# 02__RF_Power.net
KiCad netlist of a schematic drawn in Altium Designer
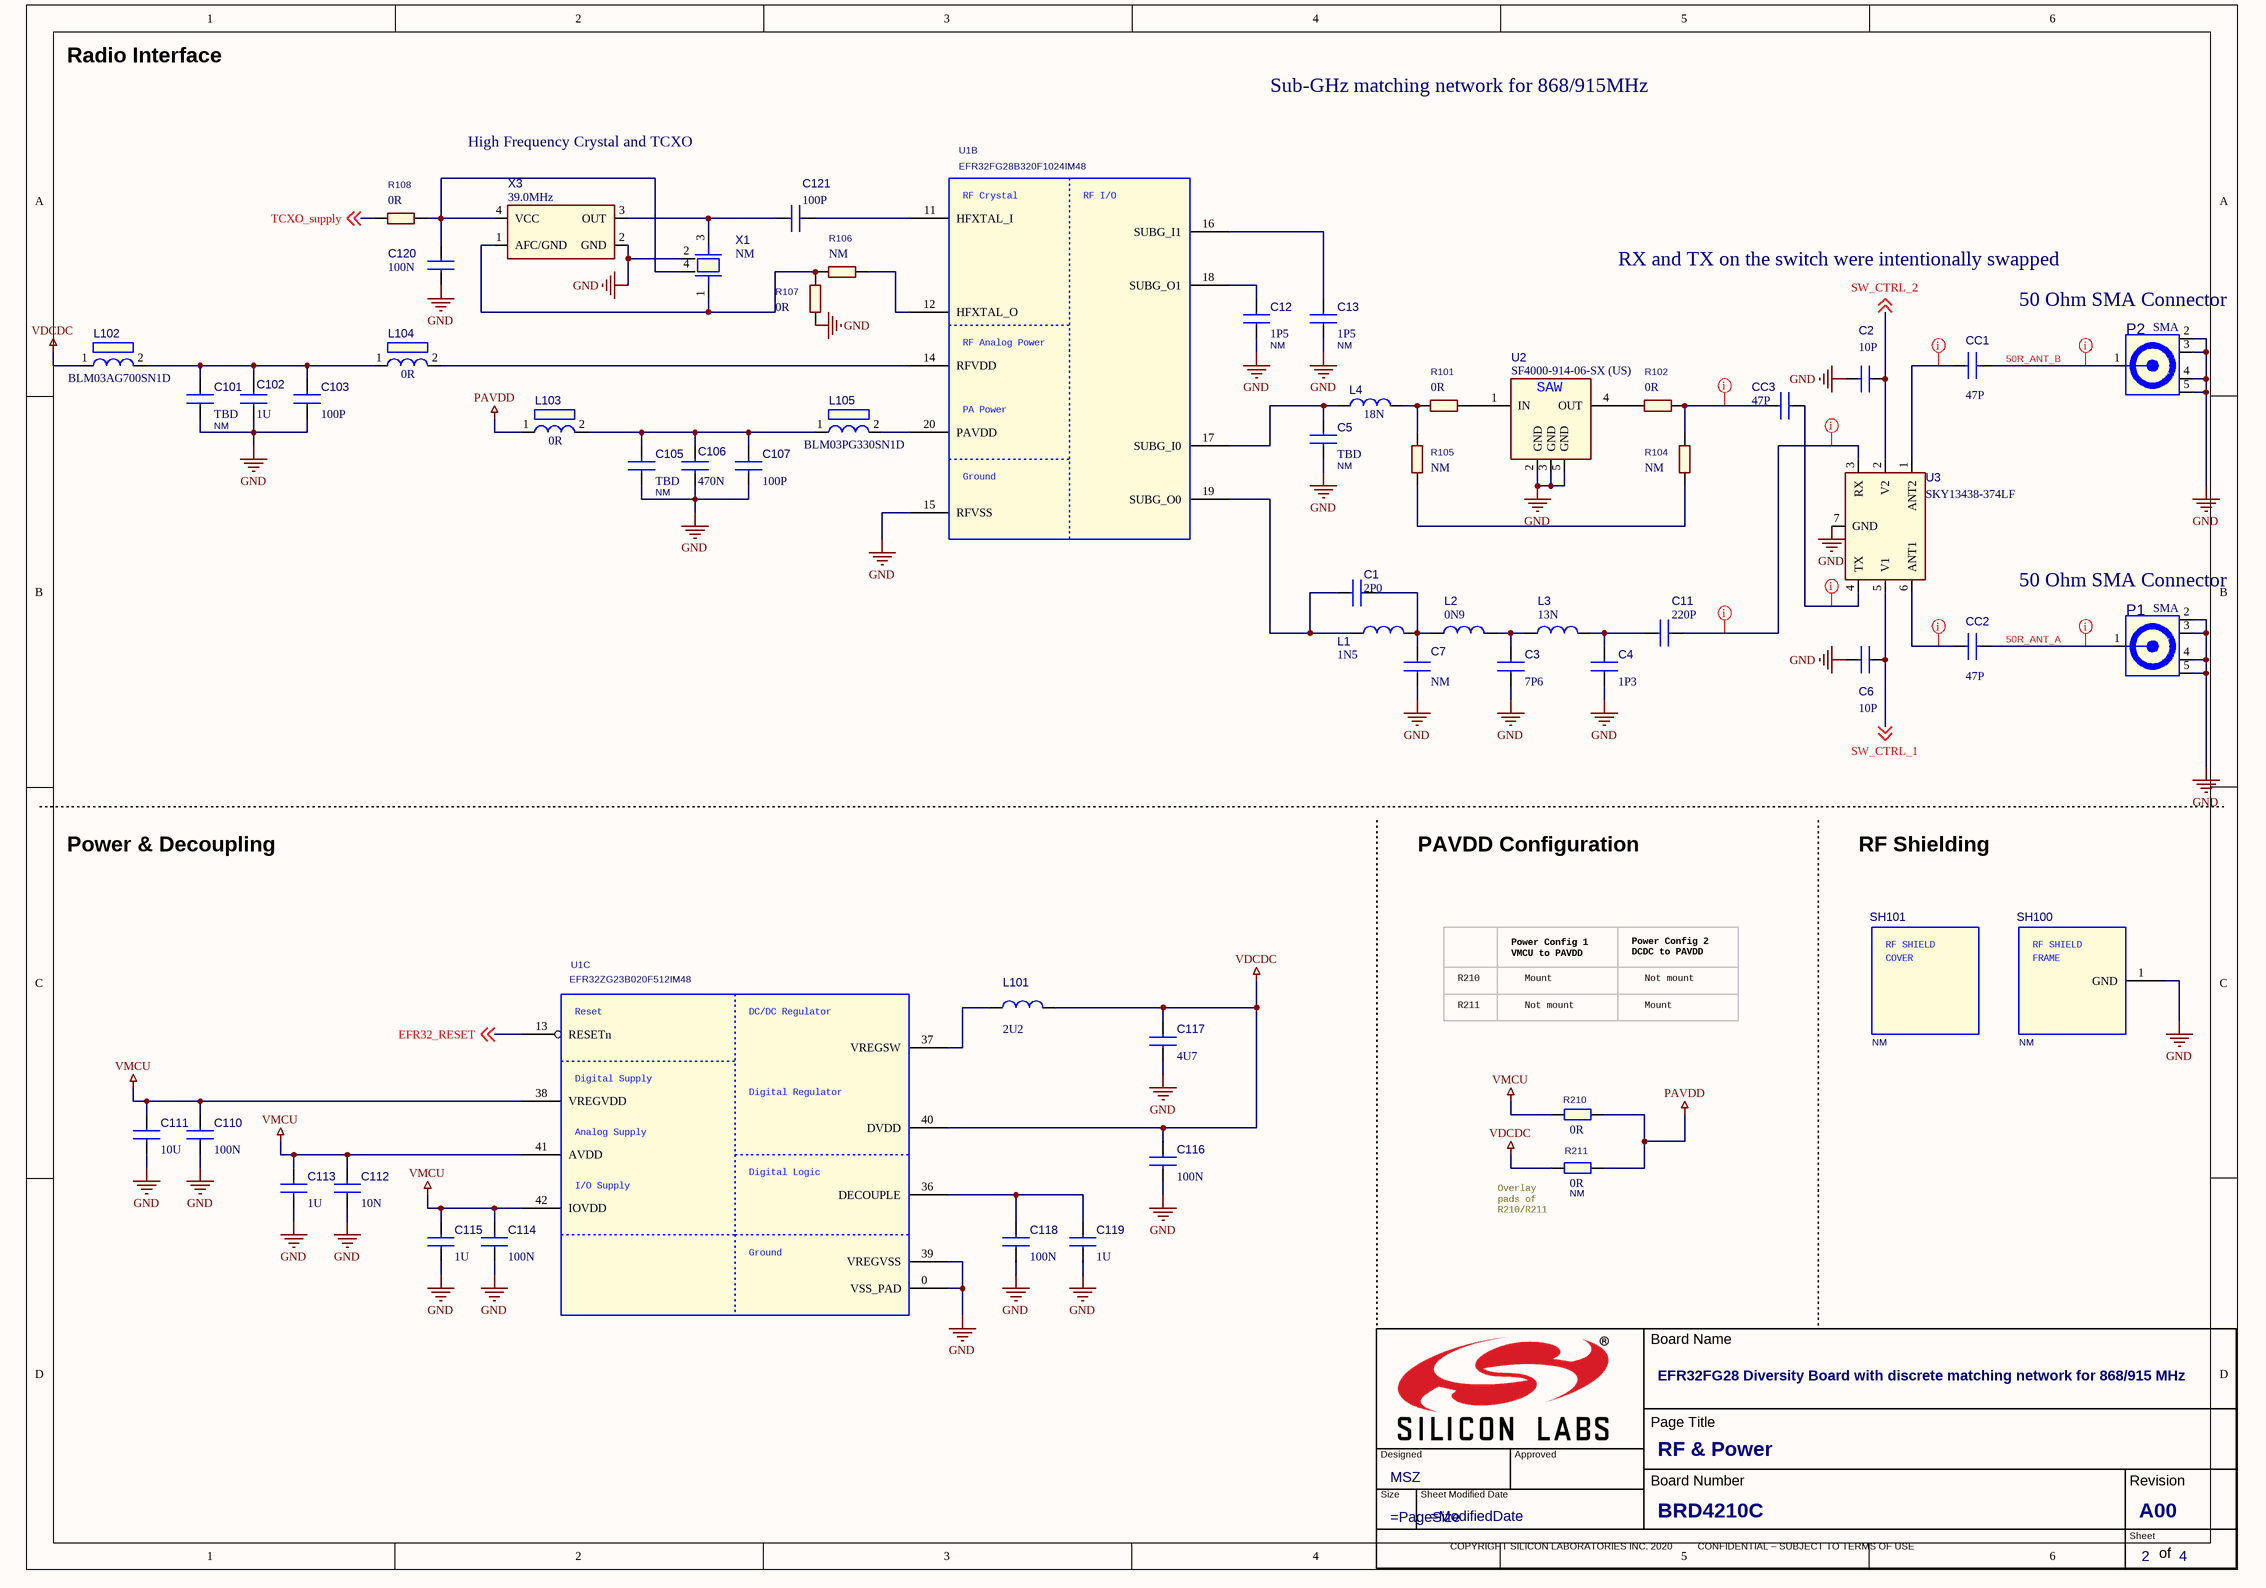
[diagram p0: 02_ RF & Power.SchDoc]

(export (version "E")
  (design (tool "Eeschema 10.0.6"))
  (components
    (comp (ref "C1")
      (value "2P0")
      (footprint "C0201_L")
      (fields (field (name "MFG") "Murata") (field (name "TOLERANCE") "±0.1pF"))
      (libsource (lib "*") (part "C0201"))
    )
    (comp (ref "C2")
      (value "10P")
      (footprint "C0201_L")
      (fields (field (name "TOLERANCE") "±2%") (field (name "MFG") "Murata"))
      (libsource (lib "*") (part "C0201"))
    )
    (comp (ref "C3")
      (value "7P6")
      (footprint "C0201_L")
      (fields (field (name "MFG") "Murata") (field (name "TOLERANCE") "±0.1pF"))
      (libsource (lib "*") (part "C0201"))
    )
    (comp (ref "C4")
      (value "1P3")
      (footprint "C0201_L")
      (fields (field (name "MFG") "Murata") (field (name "TOLERANCE") "±0.1pF"))
      (libsource (lib "*") (part "C0201"))
    )
    (comp (ref "C5")
      (value "TBD")
      (footprint "C0201_L")
      (fields (field (name "NOT MOUNTED") "NM"))
      (libsource (lib "*") (part "C0201"))
    )
    (comp (ref "C6")
      (value "10P")
      (footprint "C0201_L")
      (fields (field (name "TOLERANCE") "±2%") (field (name "MFG") "Murata"))
      (libsource (lib "*") (part "C0201"))
    )
    (comp (ref "C7")
      (value "NM")
      (footprint "C0201_L")
      (fields (field (name "MFG") "Murata") (field (name "TOLERANCE") "±0.1pF"))
      (libsource (lib "*") (part "C0201"))
    )
    (comp (ref "C11")
      (value "220P")
      (footprint "C0201_L")
      (fields (field (name "MFG") "Murata") (field (name "TOLERANCE") "±2%"))
      (libsource (lib "*") (part "C0201"))
    )
    (comp (ref "C12")
      (value "1P5")
      (footprint "C0201_L")
      (fields
        (field (name "MFG") "Murata")
        (field (name "NOT MOUNTED") "NM")
        (field (name "TOLERANCE") "±0.05pF")
      )
      (libsource (lib "*") (part "C0201"))
    )
    (comp (ref "C13")
      (value "1P5")
      (footprint "C0201_L")
      (fields
        (field (name "MFG") "Murata")
        (field (name "NOT MOUNTED") "NM")
        (field (name "TOLERANCE") "±0.05pF")
      )
      (libsource (lib "*") (part "C0201"))
    )
    (comp (ref "C101")
      (value "TBD")
      (footprint "C0201_L")
      (fields (field (name "NOT MOUNTED") "NM") (field (name "TOLERANCE") "+/-0.05P"))
      (libsource (lib "*") (part "C0201"))
    )
    (comp (ref "C102")
      (value "1U")
      (footprint "C0402_L")
      (fields (field (name "TOLERANCE") "10%"))
      (libsource (lib "*") (part "C0402"))
    )
    (comp (ref "C103")
      (value "100P")
      (footprint "C0201_L")
      (fields (field (name "TOLERANCE") "5%"))
      (libsource (lib "*") (part "C0201"))
    )
    (comp (ref "C105")
      (value "TBD")
      (footprint "C0201_L")
      (fields (field (name "NOT MOUNTED") "NM") (field (name "TOLERANCE") "+/-0.05P"))
      (libsource (lib "*") (part "C0201"))
    )
    (comp (ref "C106")
      (value "470N")
      (footprint "C0402_L")
      (fields (field (name "TOLERANCE") "10%"))
      (libsource (lib "*") (part "C0402"))
    )
    (comp (ref "C107")
      (value "100P")
      (footprint "C0201_L")
      (fields (field (name "TOLERANCE") "5%"))
      (libsource (lib "*") (part "C0201"))
    )
    (comp (ref "C110")
      (value "100N")
      (footprint "C0201_L")
      (fields (field (name "TOLERANCE") "20%"))
      (libsource (lib "*") (part "C0201"))
    )
    (comp (ref "C111")
      (value "10U")
      (footprint "C0603_L")
      (fields (field (name "TOLERANCE") "10%"))
      (libsource (lib "*") (part "C0603"))
    )
    (comp (ref "C112")
      (value "10N")
      (footprint "C0201_L")
      (fields (field (name "TOLERANCE") "10%"))
      (libsource (lib "*") (part "C0201"))
    )
    (comp (ref "C113")
      (value "1U")
      (footprint "C0402_L")
      (fields (field (name "TOLERANCE") "10%"))
      (libsource (lib "*") (part "C0402"))
    )
    (comp (ref "C114")
      (value "100N")
      (footprint "C0201_L")
      (fields (field (name "TOLERANCE") "20%"))
      (libsource (lib "*") (part "C0201"))
    )
    (comp (ref "C115")
      (value "1U")
      (footprint "C0402_L")
      (fields (field (name "TOLERANCE") "10%"))
      (libsource (lib "*") (part "C0402"))
    )
    (comp (ref "C116")
      (value "100N")
      (footprint "C0201_L")
      (fields (field (name "TOLERANCE") "20%"))
      (libsource (lib "*") (part "C0201"))
    )
    (comp (ref "C117")
      (value "4U7")
      (footprint "C0603_L")
      (fields (field (name "TOLERANCE") "10%"))
      (libsource (lib "*") (part "C0603"))
    )
    (comp (ref "C118")
      (value "100N")
      (footprint "C0201_L")
      (fields (field (name "TOLERANCE") "20%"))
      (libsource (lib "*") (part "C0201"))
    )
    (comp (ref "C119")
      (value "1U")
      (footprint "C0402_L")
      (fields (field (name "TOLERANCE") "10%"))
      (libsource (lib "*") (part "C0402"))
    )
    (comp (ref "C120")
      (value "100N")
      (footprint "C0201_L")
      (fields (field (name "MFG") "Murata") (field (name "TOLERANCE") "±0.05pF"))
      (libsource (lib "*") (part "C0201"))
    )
    (comp (ref "C121")
      (value "100P")
      (footprint "C0201_L")
      (fields (field (name "MFG") "Murata") (field (name "TOLERANCE") "±0.05pF"))
      (libsource (lib "*") (part "C0201"))
    )
    (comp (ref "CC1")
      (value "47P")
      (footprint "C0201_L")
      (fields (field (name "TOLERANCE") "±2%") (field (name "MFG") "Murata"))
      (libsource (lib "*") (part "C0201"))
    )
    (comp (ref "CC2")
      (value "47P")
      (footprint "C0201_L")
      (fields (field (name "TOLERANCE") "±2%") (field (name "MFG") "Murata"))
      (libsource (lib "*") (part "C0201"))
    )
    (comp (ref "CC3")
      (value "47P")
      (footprint "C0201_L")
      (fields (field (name "TOLERANCE") "±2%") (field (name "MFG") "Murata"))
      (libsource (lib "*") (part "C0201"))
    )
    (comp (ref "L1")
      (value "1N5")
      (footprint "COIL_0201_L")
      (fields (field (name "MFG") "Murata") (field (name "TOLERANCE") "±0.05nH"))
      (libsource (lib "*") (part "L0201"))
    )
    (comp (ref "L2")
      (value "0N9")
      (footprint "COIL_0201_L")
      (fields (field (name "MFG") "Murata") (field (name "TOLERANCE") "±0.05nH"))
      (libsource (lib "*") (part "L0201"))
    )
    (comp (ref "L3")
      (value "13N")
      (footprint "COIL_0201_L")
      (fields (field (name "MFG") "Murata") (field (name "TOLERANCE") "±3%"))
      (libsource (lib "*") (part "L0201"))
    )
    (comp (ref "L4")
      (value "18N")
      (footprint "COIL_0201_L")
      (fields (field (name "MFG") "Murata") (field (name "TOLERANCE") "±3%"))
      (libsource (lib "*") (part "L0201"))
    )
    (comp (ref "L101")
      (value "2U2")
      (footprint "COIL_1008_L")
      (fields (field (name "TOLERANCE") "+/-20%") (field (name "MFG") "Murata"))
      (libsource (lib "*") (part "L1008"))
    )
    (comp (ref "L102")
      (value "BLM03AG700SN1D")
      (footprint "COIL_MUR_BLM03_0201")
      (fields (field (name "MFG") "Murata"))
      (libsource (lib "*") (part "BLM03AX"))
    )
    (comp (ref "L103") (value "0R") (footprint "COIL_MUR_BLM03_0201") (libsource (lib "*") (part "BLM03AX")))
    (comp (ref "L104") (value "0R") (footprint "COIL_MUR_BLM03_0201") (libsource (lib "*") (part "BLM03AX")))
    (comp (ref "L105")
      (value "BLM03PG330SN1D")
      (footprint "COIL_MUR_BLM03_0201")
      (fields (field (name "MFG") "Murata"))
      (libsource (lib "*") (part "BLM03AX"))
    )
    (comp (ref "P1")
      (value "SMA")
      (footprint "TE_SMA_1814832_TH_VER")
      (fields (field (name "MFG") "Wellshow"))
      (libsource (lib "*") (part "SMA_TH_WELLSHOW"))
    )
    (comp (ref "P2")
      (value "SMA")
      (footprint "TE_SMA_1814832_TH_VER")
      (fields (field (name "MFG") "Wellshow"))
      (libsource (lib "*") (part "SMA_TH_WELLSHOW"))
    )
    (comp (ref "R101") (value "0R") (footprint "R0201_L") (libsource (lib "BRD4210A_Library") (part "R0201")))
    (comp (ref "R102") (value "0R") (footprint "R0201_L") (libsource (lib "BRD4210A_Library") (part "R0201")))
    (comp (ref "R104") (value "NM") (footprint "R0201_L") (libsource (lib "") (part "R0201_1")))
    (comp (ref "R105") (value "NM") (footprint "R0201_L") (libsource (lib "") (part "R0201_1")))
    (comp (ref "R106") (value "NM") (footprint "R0201_L") (libsource (lib "BRD4210A_Library") (part "R0201")))
    (comp (ref "R107") (value "0R") (footprint "R0201_L") (libsource (lib "") (part "R0201_1")))
    (comp (ref "R108") (value "0R") (footprint "R0201_L") (libsource (lib "BRD4210A_Library") (part "R0201")))
    (comp (ref "R210") (value "0R") (footprint "R0402_L") (libsource (lib "") (part "R0402_1")))
    (comp (ref "R211")
      (value "0R")
      (footprint "R0402_L")
      (fields (field (name "NOT MOUNTED") "NM"))
      (libsource (lib "*") (part "R0402"))
    )
    (comp (ref "SH100")
      (value "RF_SHIELD_FRAME_36103205S")
      (footprint "Shield_21x21mm")
      (fields (field (name "NOT MOUNTED") "NM") (field (name "MFG") "Würth Elektronik"))
      (libsource (lib "*") (part "RF_SHIELD_FRAME_36103205S"))
    )
    (comp (ref "SH101")
      (value "RF_SHIELD_COVER_36003200S")
      (fields (field (name "NOT MOUNTED") "NM") (field (name "MFG") "Würth Elektronik"))
      (libsource (lib "*") (part "RF_SHIELD_COVER_36003200S"))
    )
    (comp (ref "U1")
      (value "EFR32ZG23B020F512IM48")
      (footprint "QFN48_M040_6.0X6.0_EP_SL")
      (fields (field (name "MFG") "Silicon Labs"))
      (libsource (lib "*") (part "EFR32xG23_QFN48"))
    )
    (comp (ref "U2")
      (value "SF4000-914-06-SX (US)")
      (footprint "SF1256")
      (description "B2645 from Qualcomm also fits")
      (fields (field (name "MFG") "ACTE"))
      (libsource (lib "BRD4210A_Library") (part "SF4000-914-06-SX"))
    )
    (comp (ref "U3")
      (value "SKY13438-374LF")
      (footprint "SKY13438-374LF")
      (fields (field (name "MFG") "Infineon"))
      (libsource (lib "BRD4210A_Library") (part "SKY13438-374LF"))
    )
    (comp (ref "X1")
      (value "NM")
      (footprint "X_SSS_DSX211SH_2.05X1.65-4")
      (fields (field (name "MFG") "Tai-Saw"))
      (libsource (lib "*") (part "DSX211SH"))
    )
    (comp (ref "X3")
      (value "39.0MHz")
      (footprint "TCXO_7Z-38.400MBG-T_SMD2016_TXC")
      (fields (field (name "MFG") "TXC"))
      (libsource (lib "BRD4210A_Library") (part "7Z-38.400MBG-T"))
    )
  )
  (nets
    (net (code "1") (name "/50R_ANT_A") (class "Default")
      (node (ref "CC2") (pin "2") (pinfunction "2_2") (pintype "passive"))
      (node (ref "P1") (pin "1") (pinfunction "SIGNAL_1") (pintype "passive"))
    )
    (net (code "2") (name "/50R_ANT_B") (class "Default")
      (node (ref "CC1") (pin "2") (pinfunction "2_2") (pintype "passive"))
      (node (ref "P2") (pin "1") (pinfunction "SIGNAL_1") (pintype "passive"))
    )
    (net (code "3") (name "EFR32_RESET") (class "Default")
      (node (ref "U1") (pin "13") (pinfunction "RESETn_13") (pintype "passive"))
    )
    (net (code "4") (name "GND") (class "Default")
      (node (ref "C101") (pin "2") (pinfunction "2_2") (pintype "passive"))
      (node (ref "C102") (pin "2") (pinfunction "2_2") (pintype "passive"))
      (node (ref "C103") (pin "2") (pinfunction "2_2") (pintype "passive"))
      (node (ref "C105") (pin "2") (pinfunction "2_2") (pintype "passive"))
      (node (ref "C106") (pin "2") (pinfunction "2_2") (pintype "passive"))
      (node (ref "C107") (pin "2") (pinfunction "2_2") (pintype "passive"))
      (node (ref "C110") (pin "2") (pinfunction "2_2") (pintype "passive"))
      (node (ref "C111") (pin "2") (pinfunction "2_2") (pintype "passive"))
      (node (ref "C112") (pin "2") (pinfunction "2_2") (pintype "passive"))
      (node (ref "C113") (pin "2") (pinfunction "2_2") (pintype "passive"))
      (node (ref "C114") (pin "2") (pinfunction "2_2") (pintype "passive"))
      (node (ref "C115") (pin "2") (pinfunction "2_2") (pintype "passive"))
      (node (ref "C116") (pin "2") (pinfunction "2_2") (pintype "passive"))
      (node (ref "C117") (pin "2") (pinfunction "2_2") (pintype "passive"))
      (node (ref "C118") (pin "2") (pinfunction "2_2") (pintype "passive"))
      (node (ref "C119") (pin "2") (pinfunction "2_2") (pintype "passive"))
      (node (ref "C12") (pin "2") (pinfunction "2_2") (pintype "passive"))
      (node (ref "C120") (pin "2") (pinfunction "2_2") (pintype "passive"))
      (node (ref "C13") (pin "2") (pinfunction "2_2") (pintype "passive"))
      (node (ref "C2") (pin "1") (pinfunction "1_1") (pintype "passive"))
      (node (ref "C3") (pin "2") (pinfunction "2_2") (pintype "passive"))
      (node (ref "C4") (pin "2") (pinfunction "2_2") (pintype "passive"))
      (node (ref "C5") (pin "2") (pinfunction "2_2") (pintype "passive"))
      (node (ref "C6") (pin "1") (pinfunction "1_1") (pintype "passive"))
      (node (ref "C7") (pin "2") (pinfunction "2_2") (pintype "passive"))
      (node (ref "P1") (pin "2") (pinfunction "GND1_2") (pintype "passive"))
      (node (ref "P1") (pin "3") (pinfunction "GND2_3") (pintype "passive"))
      (node (ref "P1") (pin "4") (pinfunction "GND3_4") (pintype "passive"))
      (node (ref "P1") (pin "5") (pinfunction "GND4_5") (pintype "passive"))
      (node (ref "P2") (pin "2") (pinfunction "GND1_2") (pintype "passive"))
      (node (ref "P2") (pin "3") (pinfunction "GND2_3") (pintype "passive"))
      (node (ref "P2") (pin "4") (pinfunction "GND3_4") (pintype "passive"))
      (node (ref "P2") (pin "5") (pinfunction "GND4_5") (pintype "passive"))
      (node (ref "R107") (pin "2") (pinfunction "2_2") (pintype "passive"))
      (node (ref "SH100") (pin "1") (pinfunction "GND_1") (pintype "passive"))
      (node (ref "U1") (pin "0") (pinfunction "VSS_PAD_0") (pintype "power_in"))
      (node (ref "U1") (pin "15") (pinfunction "RFVSS_15") (pintype "passive"))
      (node (ref "U1") (pin "39") (pinfunction "VREGVSS_39") (pintype "passive"))
      (node (ref "U2") (pin "2") (pinfunction "GND_2") (pintype "passive"))
      (node (ref "U2") (pin "3") (pinfunction "GND_3") (pintype "passive"))
      (node (ref "U2") (pin "5") (pinfunction "GND_5") (pintype "passive"))
      (node (ref "U3") (pin "7") (pinfunction "GND_7") (pintype "passive"))
      (node (ref "X1") (pin "2") (pinfunction "2_2") (pintype "passive"))
      (node (ref "X3") (pin "2") (pinfunction "GND_2") (pintype "passive"))
    )
    (net (code "5") (name "Net-(C1-Pad2)") (class "Default")
      (node (ref "C1") (pin "2") (pinfunction "2_2") (pintype "passive"))
      (node (ref "C7") (pin "1") (pinfunction "1_1") (pintype "passive"))
      (node (ref "L1") (pin "2") (pinfunction "2_2") (pintype "passive"))
      (node (ref "L2") (pin "1") (pinfunction "1_1") (pintype "passive"))
    )
    (net (code "6") (name "Net-(C3-Pad1)") (class "Default")
      (node (ref "C3") (pin "1") (pinfunction "1_1") (pintype "passive"))
      (node (ref "L2") (pin "2") (pinfunction "2_2") (pintype "passive"))
      (node (ref "L3") (pin "1") (pinfunction "1_1") (pintype "passive"))
    )
    (net (code "7") (name "Net-(C11-Pad1)") (class "Default")
      (node (ref "C11") (pin "1") (pinfunction "1_1") (pintype "passive"))
      (node (ref "C4") (pin "1") (pinfunction "1_1") (pintype "passive"))
      (node (ref "L3") (pin "2") (pinfunction "2_2") (pintype "passive"))
    )
    (net (code "8") (name "Net-(C101-Pad1)") (class "Default")
      (node (ref "C101") (pin "1") (pinfunction "1_1") (pintype "passive"))
      (node (ref "C102") (pin "1") (pinfunction "1_1") (pintype "passive"))
      (node (ref "C103") (pin "1") (pinfunction "1_1") (pintype "passive"))
      (node (ref "L102") (pin "2") (pinfunction "2_2") (pintype "passive"))
      (node (ref "L104") (pin "1") (pinfunction "1_1") (pintype "passive"))
    )
    (net (code "9") (name "Net-(C105-Pad1)") (class "Default")
      (node (ref "C105") (pin "1") (pinfunction "1_1") (pintype "passive"))
      (node (ref "C106") (pin "1") (pinfunction "1_1") (pintype "passive"))
      (node (ref "C107") (pin "1") (pinfunction "1_1") (pintype "passive"))
      (node (ref "L103") (pin "2") (pinfunction "2_2") (pintype "passive"))
      (node (ref "L105") (pin "1") (pinfunction "1_1") (pintype "passive"))
    )
    (net (code "10") (name "Net-(CC3-Pad1)") (class "Default")
      (node (ref "CC3") (pin "1") (pinfunction "1_1") (pintype "passive"))
      (node (ref "R102") (pin "2") (pinfunction "2_2") (pintype "passive"))
      (node (ref "R104") (pin "1") (pinfunction "1_1") (pintype "passive"))
    )
    (net (code "11") (name "Net-(L4-Pad2)") (class "Default")
      (node (ref "L4") (pin "2") (pinfunction "2_2") (pintype "passive"))
      (node (ref "R101") (pin "1") (pinfunction "1_1") (pintype "passive"))
      (node (ref "R105") (pin "1") (pinfunction "1_1") (pintype "passive"))
    )
    (net (code "12") (name "Net-(R104-Pad2)") (class "Default")
      (node (ref "R104") (pin "2") (pinfunction "2_2") (pintype "passive"))
      (node (ref "R105") (pin "2") (pinfunction "2_2") (pintype "passive"))
    )
    (net (code "13") (name "Net-(U1B-HFXTAL_I)") (class "Default")
      (node (ref "C121") (pin "2") (pinfunction "2_2") (pintype "passive"))
      (node (ref "U1") (pin "11") (pinfunction "HFXTAL_I_11") (pintype "passive"))
    )
    (net (code "14") (name "Net-(U1B-HFXTAL_O)") (class "Default")
      (node (ref "R106") (pin "2") (pinfunction "2_2") (pintype "passive"))
      (node (ref "U1") (pin "12") (pinfunction "HFXTAL_O_12") (pintype "passive"))
    )
    (net (code "15") (name "Net-(U1B-PAVDD)") (class "Default")
      (node (ref "L105") (pin "2") (pinfunction "2_2") (pintype "passive"))
      (node (ref "U1") (pin "20") (pinfunction "PAVDD_20") (pintype "passive"))
    )
    (net (code "16") (name "Net-(U1B-RFVDD)") (class "Default")
      (node (ref "L104") (pin "2") (pinfunction "2_2") (pintype "passive"))
      (node (ref "U1") (pin "14") (pinfunction "RFVDD_14") (pintype "power_in"))
    )
    (net (code "17") (name "Net-(U1B-SUBG_I0)") (class "Default")
      (node (ref "C5") (pin "1") (pinfunction "1_1") (pintype "passive"))
      (node (ref "L4") (pin "1") (pinfunction "1_1") (pintype "passive"))
      (node (ref "U1") (pin "17") (pinfunction "SUBG_I0_17") (pintype "passive"))
    )
    (net (code "18") (name "Net-(U1B-SUBG_I1)") (class "Default")
      (node (ref "C13") (pin "1") (pinfunction "1_1") (pintype "passive"))
      (node (ref "U1") (pin "16") (pinfunction "SUBG_I1_16") (pintype "passive"))
    )
    (net (code "19") (name "Net-(U1B-SUBG_O0)") (class "Default")
      (node (ref "C1") (pin "1") (pinfunction "1_1") (pintype "passive"))
      (node (ref "L1") (pin "1") (pinfunction "1_1") (pintype "passive"))
      (node (ref "U1") (pin "19") (pinfunction "SUBG_O0_19") (pintype "passive"))
    )
    (net (code "20") (name "Net-(U1B-SUBG_O1)") (class "Default")
      (node (ref "C12") (pin "1") (pinfunction "1_1") (pintype "passive"))
      (node (ref "U1") (pin "18") (pinfunction "SUBG_O1_18") (pintype "passive"))
    )
    (net (code "21") (name "Net-(U1C-DECOUPLE)") (class "Default")
      (node (ref "C118") (pin "1") (pinfunction "1_1") (pintype "passive"))
      (node (ref "C119") (pin "1") (pinfunction "1_1") (pintype "passive"))
      (node (ref "U1") (pin "36") (pinfunction "DECOUPLE_36") (pintype "power_in"))
    )
    (net (code "22") (name "Net-(U1C-VREGSW)") (class "Default")
      (node (ref "L101") (pin "1") (pinfunction "1_1") (pintype "passive"))
      (node (ref "U1") (pin "37") (pinfunction "VREGSW_37") (pintype "passive"))
    )
    (net (code "23") (name "Net-(U2-IN)") (class "Default")
      (node (ref "R101") (pin "2") (pinfunction "2_2") (pintype "passive"))
      (node (ref "U2") (pin "1") (pinfunction "IN_1") (pintype "passive"))
    )
    (net (code "24") (name "Net-(U2-OUT)") (class "Default")
      (node (ref "R102") (pin "1") (pinfunction "1_1") (pintype "passive"))
      (node (ref "U2") (pin "4") (pinfunction "OUT_4") (pintype "passive"))
    )
    (net (code "25") (name "Net-(U3-ANT1)") (class "Default")
      (node (ref "CC2") (pin "1") (pinfunction "1_1") (pintype "passive"))
      (node (ref "U3") (pin "6") (pinfunction "ANT1_6") (pintype "passive"))
    )
    (net (code "26") (name "Net-(U3-ANT2)") (class "Default")
      (node (ref "CC1") (pin "1") (pinfunction "1_1") (pintype "passive"))
      (node (ref "U3") (pin "1") (pinfunction "ANT2_1") (pintype "passive"))
    )
    (net (code "27") (name "Net-(U3-RX)") (class "Default")
      (node (ref "C11") (pin "2") (pinfunction "2_2") (pintype "passive"))
      (node (ref "U3") (pin "3") (pinfunction "RX_3") (pintype "passive"))
    )
    (net (code "28") (name "Net-(U3-TX)") (class "Default")
      (node (ref "CC3") (pin "2") (pinfunction "2_2") (pintype "passive"))
      (node (ref "U3") (pin "4") (pinfunction "TX_4") (pintype "passive"))
    )
    (net (code "29") (name "Net-(X3-AFC{slash}GND)") (class "Default")
      (node (ref "R106") (pin "1") (pinfunction "1_1") (pintype "passive"))
      (node (ref "R107") (pin "1") (pinfunction "1_1") (pintype "passive"))
      (node (ref "X1") (pin "1") (pinfunction "1_1") (pintype "passive"))
      (node (ref "X3") (pin "1") (pinfunction "AFC/GND_1") (pintype "passive"))
    )
    (net (code "30") (name "Net-(X3-OUT)") (class "Default")
      (node (ref "C121") (pin "1") (pinfunction "1_1") (pintype "passive"))
      (node (ref "X1") (pin "3") (pinfunction "3_3") (pintype "passive"))
      (node (ref "X3") (pin "3") (pinfunction "OUT_3") (pintype "passive"))
    )
    (net (code "31") (name "Net-(X3-VCC)") (class "Default")
      (node (ref "C120") (pin "1") (pinfunction "1_1") (pintype "passive"))
      (node (ref "R108") (pin "2") (pinfunction "2_2") (pintype "passive"))
      (node (ref "X1") (pin "4") (pinfunction "4_4") (pintype "passive"))
      (node (ref "X3") (pin "4") (pinfunction "VCC_4") (pintype "passive"))
    )
    (net (code "32") (name "PAVDD") (class "Default")
      (node (ref "L103") (pin "1") (pinfunction "1_1") (pintype "passive"))
      (node (ref "R210") (pin "1") (pinfunction "1_1") (pintype "passive"))
      (node (ref "R211") (pin "2") (pinfunction "2_2") (pintype "passive"))
    )
    (net (code "33") (name "SW_CTRL_1") (class "Default")
      (node (ref "C6") (pin "2") (pinfunction "2_2") (pintype "passive"))
      (node (ref "U3") (pin "5") (pinfunction "V1_5") (pintype "passive"))
    )
    (net (code "34") (name "SW_CTRL_2") (class "Default")
      (node (ref "C2") (pin "2") (pinfunction "2_2") (pintype "passive"))
      (node (ref "U3") (pin "2") (pinfunction "V2_2") (pintype "passive"))
    )
    (net (code "35") (name "TCXO_supply") (class "Default")
      (node (ref "R108") (pin "1") (pinfunction "1_1") (pintype "passive"))
    )
    (net (code "36") (name "VDCDC") (class "Default")
      (node (ref "C116") (pin "1") (pinfunction "1_1") (pintype "passive"))
      (node (ref "C117") (pin "1") (pinfunction "1_1") (pintype "passive"))
      (node (ref "L101") (pin "2") (pinfunction "2_2") (pintype "passive"))
      (node (ref "L102") (pin "1") (pinfunction "1_1") (pintype "passive"))
      (node (ref "R211") (pin "1") (pinfunction "1_1") (pintype "passive"))
      (node (ref "U1") (pin "40") (pinfunction "DVDD_40") (pintype "power_in"))
    )
    (net (code "37") (name "VMCU") (class "Default")
      (node (ref "C110") (pin "1") (pinfunction "1_1") (pintype "passive"))
      (node (ref "C111") (pin "1") (pinfunction "1_1") (pintype "passive"))
      (node (ref "C112") (pin "1") (pinfunction "1_1") (pintype "passive"))
      (node (ref "C113") (pin "1") (pinfunction "1_1") (pintype "passive"))
      (node (ref "C114") (pin "1") (pinfunction "1_1") (pintype "passive"))
      (node (ref "C115") (pin "1") (pinfunction "1_1") (pintype "passive"))
      (node (ref "R210") (pin "2") (pinfunction "2_2") (pintype "passive"))
      (node (ref "U1") (pin "38") (pinfunction "VREGVDD_38") (pintype "passive"))
      (node (ref "U1") (pin "41") (pinfunction "AVDD_41") (pintype "power_in"))
      (node (ref "U1") (pin "42") (pinfunction "IOVDD_42") (pintype "power_in"))
    )
  )
)
